# Row.net
KiCad netlist of a schematic drawn in Altium Designer
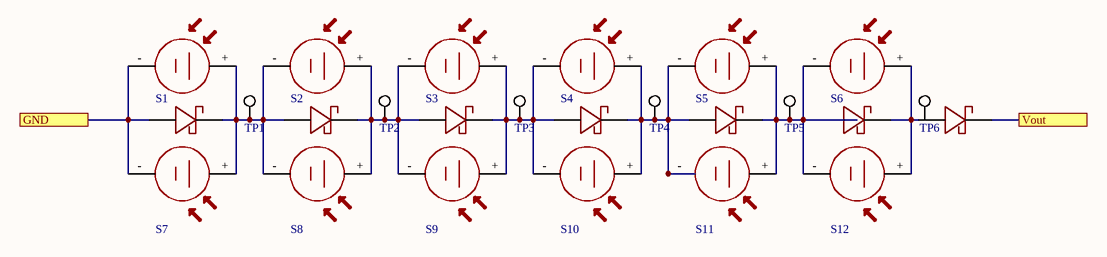
[diagram p0: Row.SchDoc]

(export (version "E")
  (design (tool "Eeschema 10.0.6"))
  (components
    (comp (ref "D1")
      (value "SCHOTTKY_DIODE_B120-FDICT-NDSCHOTTKY_DIODE_B120-FDICT-ND")
      (footprint "SB_DIODE")
      (fields (field (name "LIBRARYNAME") "Solar_Fadi"))
      (libsource (lib "SchLib") (part "SCHOTTKY_DIODE_B120-FDICT-NDSCHOTTKY_DIODE_B120-FDICT-ND"))
    )
    (comp (ref "D2")
      (value "SCHOTTKY_DIODE_B120-FDICT-NDSCHOTTKY_DIODE_B120-FDICT-ND")
      (footprint "SB_DIODE")
      (fields (field (name "LIBRARYNAME") "Solar_Fadi"))
      (libsource (lib "SchLib") (part "SCHOTTKY_DIODE_B120-FDICT-NDSCHOTTKY_DIODE_B120-FDICT-ND"))
    )
    (comp (ref "D3")
      (value "SCHOTTKY_DIODE_B120-FDICT-NDSCHOTTKY_DIODE_B120-FDICT-ND")
      (footprint "SB_DIODE")
      (fields (field (name "LIBRARYNAME") "Solar_Fadi"))
      (libsource (lib "SchLib") (part "SCHOTTKY_DIODE_B120-FDICT-NDSCHOTTKY_DIODE_B120-FDICT-ND"))
    )
    (comp (ref "D4")
      (value "SCHOTTKY_DIODE_B120-FDICT-NDSCHOTTKY_DIODE_B120-FDICT-ND")
      (footprint "SB_DIODE")
      (fields (field (name "LIBRARYNAME") "Solar_Fadi"))
      (libsource (lib "SchLib") (part "SCHOTTKY_DIODE_B120-FDICT-NDSCHOTTKY_DIODE_B120-FDICT-ND"))
    )
    (comp (ref "D5")
      (value "SCHOTTKY_DIODE_B120-FDICT-NDSCHOTTKY_DIODE_B120-FDICT-ND")
      (footprint "SB_DIODE")
      (fields (field (name "LIBRARYNAME") "Solar_Fadi"))
      (libsource (lib "SchLib") (part "SCHOTTKY_DIODE_B120-FDICT-NDSCHOTTKY_DIODE_B120-FDICT-ND"))
    )
    (comp (ref "D6")
      (value "SCHOTTKY_DIODE_B120-FDICT-NDSCHOTTKY_DIODE_B120-FDICT-ND")
      (footprint "SB_DIODE")
      (fields (field (name "LIBRARYNAME") "Solar_Fadi"))
      (libsource (lib "") (part "SCHOTTKY_DIODE_B120-FDICT-NDSCHOTTKY_DIODE_B120-FDICT-ND_1"))
    )
    (comp (ref "D7")
      (value "SCHOTTKY_DIODE_B120-FDICT-NDSCHOTTKY_DIODE_B120-FDICT-ND")
      (footprint "SB_DIODE")
      (fields (field (name "LIBRARYNAME") "Solar_Fadi"))
      (libsource (lib "SchLib") (part "SCHOTTKY_DIODE_B120-FDICT-NDSCHOTTKY_DIODE_B120-FDICT-ND"))
    )
    (comp (ref "S1")
      (value "SOLAR_CELL")
      (footprint "SOLAR_CELL")
      (libsource (lib "SchLib") (part "SOLAR_CELL"))
    )
    (comp (ref "S2")
      (value "SOLAR_CELL")
      (footprint "SOLAR_CELL")
      (libsource (lib "SchLib") (part "SOLAR_CELL"))
    )
    (comp (ref "S3")
      (value "SOLAR_CELL")
      (footprint "SOLAR_CELL")
      (libsource (lib "SchLib") (part "SOLAR_CELL"))
    )
    (comp (ref "S4")
      (value "SOLAR_CELL")
      (footprint "SOLAR_CELL")
      (libsource (lib "SchLib") (part "SOLAR_CELL"))
    )
    (comp (ref "S5")
      (value "SOLAR_CELL")
      (footprint "SOLAR_CELL")
      (libsource (lib "SchLib") (part "SOLAR_CELL"))
    )
    (comp (ref "S6")
      (value "SOLAR_CELL")
      (footprint "SOLAR_CELL")
      (libsource (lib "SchLib") (part "SOLAR_CELL"))
    )
    (comp (ref "S7")
      (value "SOLAR_CELL")
      (footprint "SOLAR_CELL")
      (libsource (lib "SchLib") (part "SOLAR_CELL"))
    )
    (comp (ref "S8")
      (value "SOLAR_CELL")
      (footprint "SOLAR_CELL")
      (libsource (lib "SchLib") (part "SOLAR_CELL"))
    )
    (comp (ref "S9")
      (value "SOLAR_CELL")
      (footprint "SOLAR_CELL")
      (libsource (lib "SchLib") (part "SOLAR_CELL"))
    )
    (comp (ref "S10")
      (value "SOLAR_CELL")
      (footprint "SOLAR_CELL")
      (libsource (lib "SchLib") (part "SOLAR_CELL"))
    )
    (comp (ref "S11")
      (value "SOLAR_CELL")
      (footprint "SOLAR_CELL")
      (libsource (lib "SchLib") (part "SOLAR_CELL"))
    )
    (comp (ref "S12")
      (value "SOLAR_CELL")
      (footprint "SOLAR_CELL")
      (libsource (lib "SchLib") (part "SOLAR_CELL"))
    )
    (comp (ref "TP1")
      (value "TEST_POINT")
      (footprint "TEST_POINT")
      (libsource (lib "SchLib") (part "TEST_POINT"))
    )
    (comp (ref "TP2")
      (value "TEST_POINT")
      (footprint "TEST_POINT")
      (libsource (lib "SchLib") (part "TEST_POINT"))
    )
    (comp (ref "TP3")
      (value "TEST_POINT")
      (footprint "TEST_POINT")
      (libsource (lib "SchLib") (part "TEST_POINT"))
    )
    (comp (ref "TP4")
      (value "TEST_POINT")
      (footprint "TEST_POINT")
      (libsource (lib "SchLib") (part "TEST_POINT"))
    )
    (comp (ref "TP5")
      (value "TEST_POINT")
      (footprint "TEST_POINT")
      (libsource (lib "SchLib") (part "TEST_POINT"))
    )
    (comp (ref "TP6")
      (value "TEST_POINT")
      (footprint "TEST_POINT")
      (libsource (lib "SchLib") (part "TEST_POINT"))
    )
  )
  (nets
    (net (code "1") (name "/GND") (class "Default")
      (node (ref "D1") (pin "POS") (pinfunction "POS_POS") (pintype "passive"))
      (node (ref "S1") (pin "-") (pinfunction "-_-") (pintype "passive"))
      (node (ref "S7") (pin "-") (pinfunction "-_-") (pintype "passive"))
    )
    (net (code "2") (name "/Vout") (class "Default")
      (node (ref "D7") (pin "NEG") (pinfunction "NEG_NEG") (pintype "passive"))
    )
    (net (code "3") (name "Net-(D1-PadNEG)") (class "Default")
      (node (ref "D1") (pin "NEG") (pinfunction "NEG_NEG") (pintype "passive"))
      (node (ref "D2") (pin "POS") (pinfunction "POS_POS") (pintype "passive"))
      (node (ref "S1") (pin "+") (pinfunction "+_+") (pintype "passive"))
      (node (ref "S2") (pin "-") (pinfunction "-_-") (pintype "passive"))
      (node (ref "S7") (pin "+") (pinfunction "+_+") (pintype "passive"))
      (node (ref "S8") (pin "-") (pinfunction "-_-") (pintype "passive"))
      (node (ref "TP1") (pin "38") (pinfunction "38_38") (pintype "passive"))
    )
    (net (code "4") (name "Net-(D2-PadNEG)") (class "Default")
      (node (ref "D2") (pin "NEG") (pinfunction "NEG_NEG") (pintype "passive"))
      (node (ref "D3") (pin "POS") (pinfunction "POS_POS") (pintype "passive"))
      (node (ref "S2") (pin "+") (pinfunction "+_+") (pintype "passive"))
      (node (ref "S3") (pin "-") (pinfunction "-_-") (pintype "passive"))
      (node (ref "S8") (pin "+") (pinfunction "+_+") (pintype "passive"))
      (node (ref "S9") (pin "-") (pinfunction "-_-") (pintype "passive"))
      (node (ref "TP2") (pin "38") (pinfunction "38_38") (pintype "passive"))
    )
    (net (code "5") (name "Net-(D3-PadNEG)") (class "Default")
      (node (ref "D3") (pin "NEG") (pinfunction "NEG_NEG") (pintype "passive"))
      (node (ref "D4") (pin "POS") (pinfunction "POS_POS") (pintype "passive"))
      (node (ref "S10") (pin "-") (pinfunction "-_-") (pintype "passive"))
      (node (ref "S3") (pin "+") (pinfunction "+_+") (pintype "passive"))
      (node (ref "S4") (pin "-") (pinfunction "-_-") (pintype "passive"))
      (node (ref "S9") (pin "+") (pinfunction "+_+") (pintype "passive"))
      (node (ref "TP3") (pin "38") (pinfunction "38_38") (pintype "passive"))
    )
    (net (code "6") (name "Net-(D4-PadNEG)") (class "Default")
      (node (ref "D4") (pin "NEG") (pinfunction "NEG_NEG") (pintype "passive"))
      (node (ref "D5") (pin "POS") (pinfunction "POS_POS") (pintype "passive"))
      (node (ref "S10") (pin "+") (pinfunction "+_+") (pintype "passive"))
      (node (ref "S11") (pin "-") (pinfunction "-_-") (pintype "passive"))
      (node (ref "S4") (pin "+") (pinfunction "+_+") (pintype "passive"))
      (node (ref "S5") (pin "-") (pinfunction "-_-") (pintype "passive"))
      (node (ref "TP4") (pin "38") (pinfunction "38_38") (pintype "passive"))
    )
    (net (code "7") (name "Net-(D5-PadNEG)") (class "Default")
      (node (ref "D5") (pin "NEG") (pinfunction "NEG_NEG") (pintype "passive"))
      (node (ref "S11") (pin "+") (pinfunction "+_+") (pintype "passive"))
      (node (ref "S12") (pin "-") (pinfunction "-_-") (pintype "passive"))
      (node (ref "S5") (pin "+") (pinfunction "+_+") (pintype "passive"))
      (node (ref "S6") (pin "-") (pinfunction "-_-") (pintype "passive"))
      (node (ref "TP5") (pin "38") (pinfunction "38_38") (pintype "passive"))
    )
    (net (code "8") (name "Net-(D6-PadNEG)") (class "Default")
      (node (ref "D6") (pin "NEG") (pinfunction "NEG_NEG") (pintype "passive"))
      (node (ref "D7") (pin "POS") (pinfunction "POS_POS") (pintype "passive"))
      (node (ref "S12") (pin "+") (pinfunction "+_+") (pintype "passive"))
      (node (ref "S6") (pin "+") (pinfunction "+_+") (pintype "passive"))
    )
    (net (code "9") (name "unconnected-(TP6-Pad38)") (class "Default")
      (node (ref "TP6") (pin "38") (pinfunction "38_38") (pintype "passive"))
    )
  )
)
